# 09_EXP_CN_100PIN.net
KiCad netlist of a schematic drawn in Altium Designer
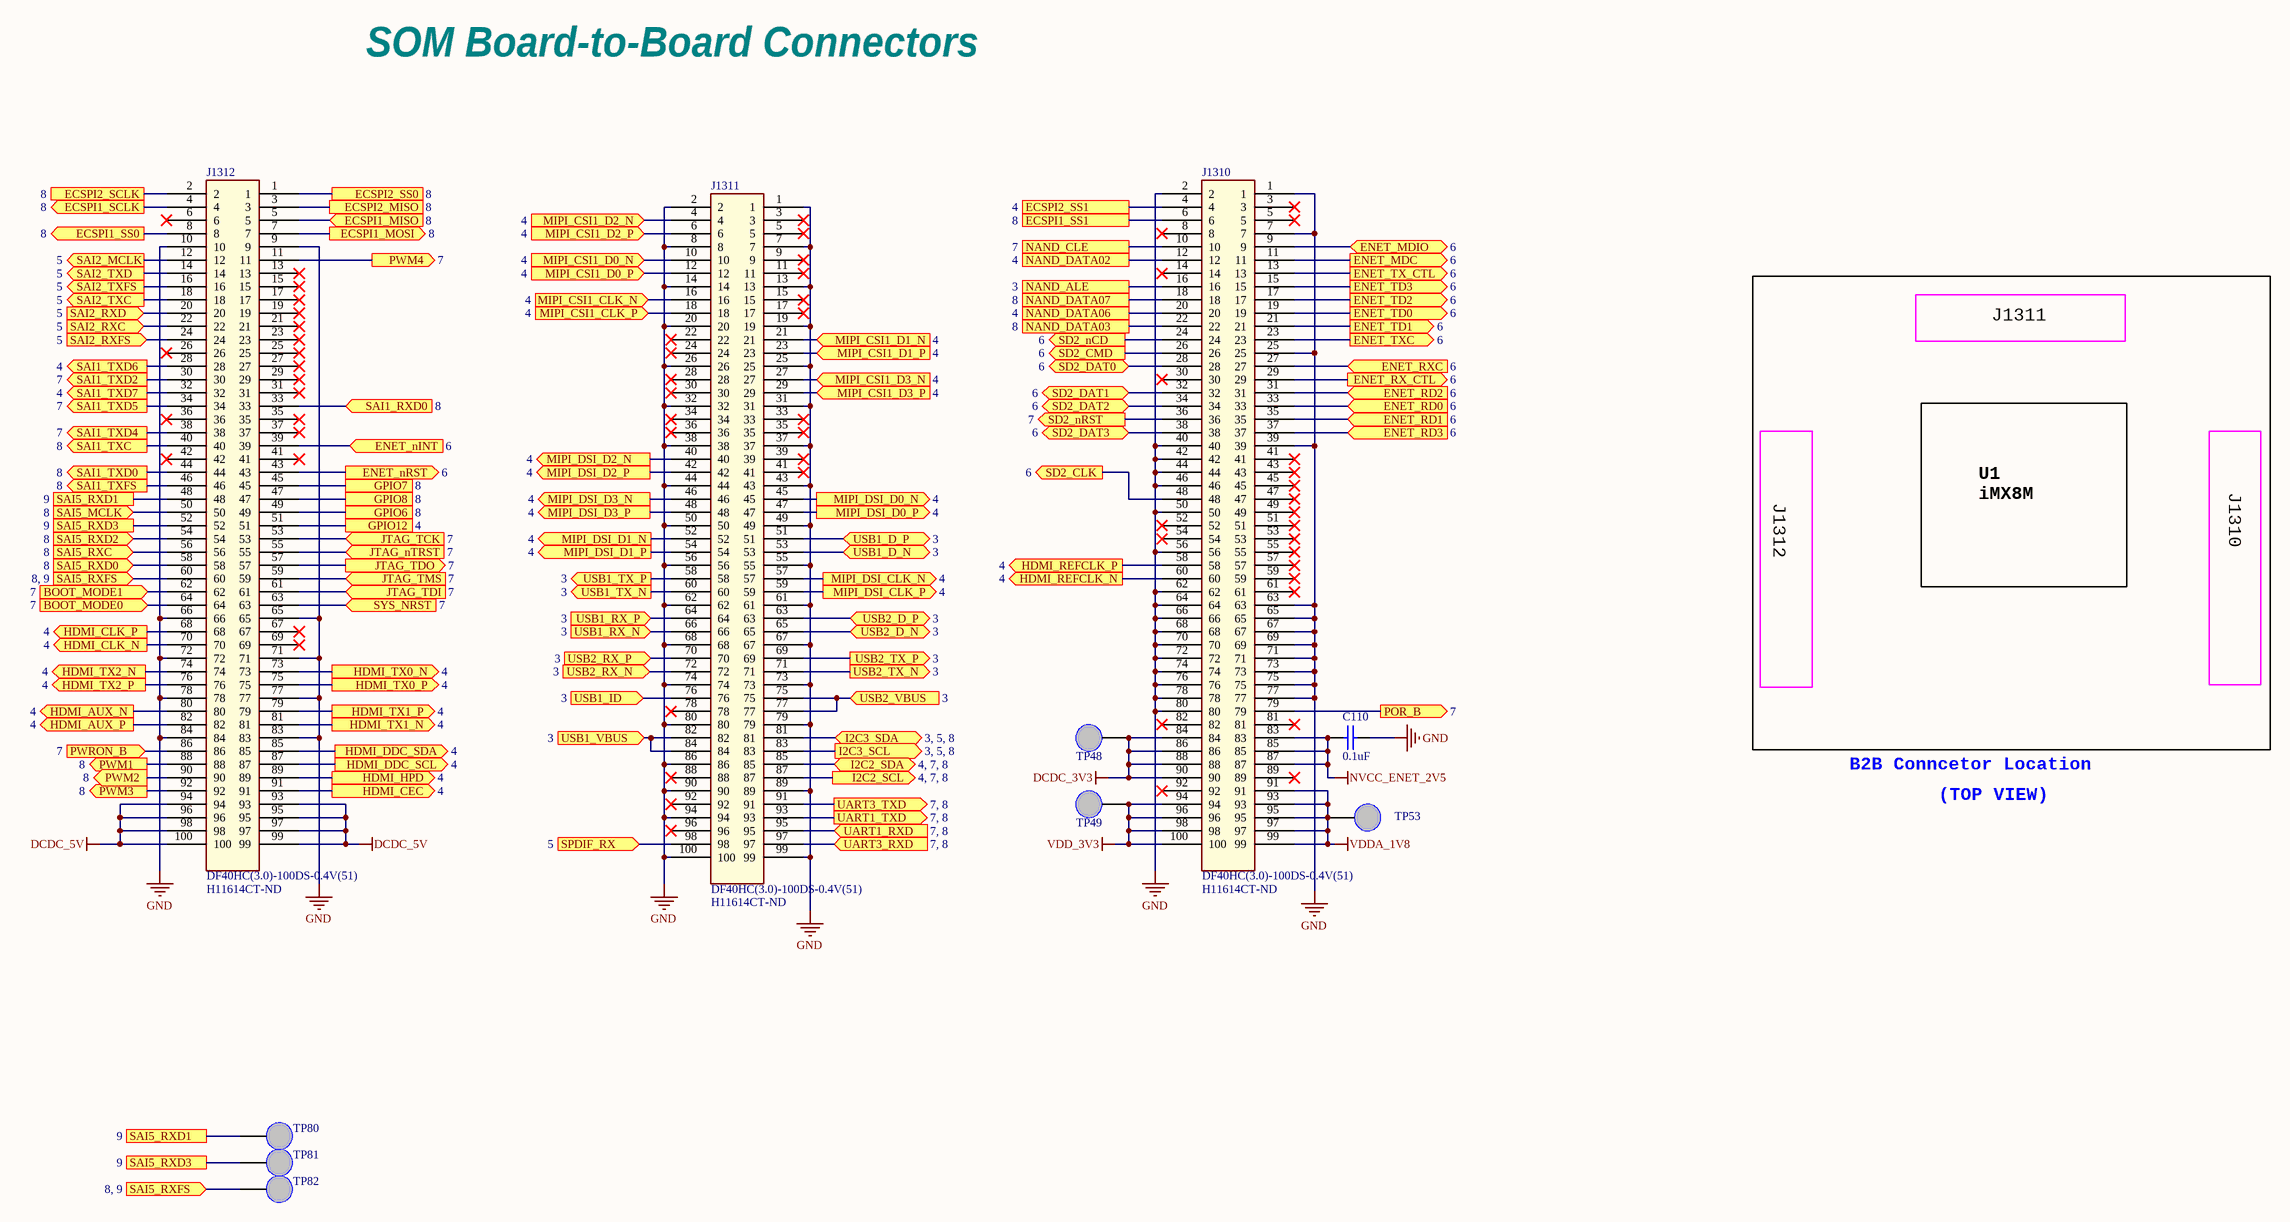
[diagram p0: 09_EXP_CN_100PIN.SchDoc]

(export (version "E")
  (design (tool "Eeschema 10.0.6"))
  (components
    (comp (ref "C110")
      (value "0.1uF")
      (footprint "0201")
      (description "CAP CER 0.1UF 10V 10% X5R 0201")
      (fields (field (name "MPN") "C0603X5R1A104K030BC") (field (name "Comment") "0.1uF/10V"))
      (libsource (lib "links") (part "CAP_0201_0.1uF"))
    )
    (comp (ref "J1310")
      (value "DF40HC(3.0)-100DS-0.4V(51)")
      (footprint "DF40HC-3_0-100DS-0_4V-51")
      (description "CONN HDR 100POS 0.4MM SMD GOLD")
      (fields (field (name "SUPPLIER PART NUMBER 1") "H11614CT-ND"))
      (libsource (lib "SpacePark") (part "CONN_HIROSE-DF40C-100DP-0.4V(51)"))
    )
    (comp (ref "J1311")
      (value "DF40HC(3.0)-100DS-0.4V(51)")
      (footprint "DF40HC-3_0-100DS-0_4V-51")
      (description "CONN HDR 100POS 0.4MM SMD GOLD")
      (fields (field (name "SUPPLIER PART NUMBER 1") "H11614CT-ND"))
      (libsource (lib "SpacePark") (part "CONN_HIROSE-DF40C-100DP-0.4V(51)"))
    )
    (comp (ref "J1312")
      (value "DF40HC(3.0)-100DS-0.4V(51)")
      (footprint "DF40HC-3_0-100DS-0_4V-51")
      (description "CONN HDR 100POS 0.4MM SMD GOLD")
      (fields (field (name "SUPPLIER PART NUMBER 1") "H11614CT-ND"))
      (libsource (lib "SpacePark") (part "CONN_HIROSE-DF40C-100DP-0.4V(51)"))
    )
    (comp (ref "TP48")
      (value "TP NM")
      (footprint "TP_SMD_L")
      (description "TEST POINT (Large)")
      (libsource (lib "links") (part "TP_L"))
    )
    (comp (ref "TP49")
      (value "TP NM")
      (footprint "TP_SMD_L")
      (description "TEST POINT (Large)")
      (libsource (lib "links") (part "TP_L"))
    )
    (comp (ref "TP53")
      (value "TP NM")
      (footprint "TP_SMD_L")
      (description "TEST POINT (Large)")
      (libsource (lib "links") (part "TP_L"))
    )
    (comp (ref "TP80")
      (value "TP NM")
      (footprint "TP_SMD_L")
      (description "TEST POINT (Large)")
      (libsource (lib "links") (part "TP_L"))
    )
    (comp (ref "TP81")
      (value "TP NM")
      (footprint "TP_SMD_L")
      (description "TEST POINT (Large)")
      (libsource (lib "links") (part "TP_L"))
    )
    (comp (ref "TP82")
      (value "TP NM")
      (footprint "TP_SMD_L")
      (description "TEST POINT (Large)")
      (libsource (lib "links") (part "TP_L"))
    )
  )
  (nets
    (net (code "1") (name "/BOOT_MODE0") (class "Default")
      (node (ref "J1312") (pin "64") (pinfunction "64_64") (pintype "passive"))
    )
    (net (code "2") (name "/BOOT_MODE1") (class "Default")
      (node (ref "J1312") (pin "62") (pinfunction "62_62") (pintype "passive"))
    )
    (net (code "3") (name "/ECSPI1_MISO") (class "Default")
      (node (ref "J1312") (pin "5") (pinfunction "5_5") (pintype "passive"))
    )
    (net (code "4") (name "/ECSPI1_MOSI") (class "Default")
      (node (ref "J1312") (pin "7") (pinfunction "7_7") (pintype "passive"))
    )
    (net (code "5") (name "/ECSPI1_SCLK") (class "Default")
      (node (ref "J1312") (pin "4") (pinfunction "4_4") (pintype "passive"))
    )
    (net (code "6") (name "/ECSPI1_SS0") (class "Default")
      (node (ref "J1312") (pin "8") (pinfunction "8_8") (pintype "passive"))
    )
    (net (code "7") (name "/ECSPI1_SS1") (class "Default")
      (node (ref "J1310") (pin "6") (pinfunction "6_6") (pintype "passive"))
    )
    (net (code "8") (name "/ECSPI2_MISO") (class "Default")
      (node (ref "J1312") (pin "3") (pinfunction "3_3") (pintype "passive"))
    )
    (net (code "9") (name "/ECSPI2_SCLK") (class "Default")
      (node (ref "J1312") (pin "2") (pinfunction "2_2") (pintype "passive"))
    )
    (net (code "10") (name "/ECSPI2_SS0") (class "Default")
      (node (ref "J1312") (pin "1") (pinfunction "1_1") (pintype "passive"))
    )
    (net (code "11") (name "/ECSPI2_SS1") (class "Default")
      (node (ref "J1310") (pin "4") (pinfunction "4_4") (pintype "passive"))
    )
    (net (code "12") (name "/ENET_MDC") (class "Default")
      (node (ref "J1310") (pin "11") (pinfunction "11_11") (pintype "passive"))
    )
    (net (code "13") (name "/ENET_MDIO") (class "Default")
      (node (ref "J1310") (pin "9") (pinfunction "9_9") (pintype "passive"))
    )
    (net (code "14") (name "/ENET_RD0") (class "Default")
      (node (ref "J1310") (pin "33") (pinfunction "33_33") (pintype "passive"))
    )
    (net (code "15") (name "/ENET_RD1") (class "Default")
      (node (ref "J1310") (pin "35") (pinfunction "35_35") (pintype "passive"))
    )
    (net (code "16") (name "/ENET_RD2") (class "Default")
      (node (ref "J1310") (pin "31") (pinfunction "31_31") (pintype "passive"))
    )
    (net (code "17") (name "/ENET_RD3") (class "Default")
      (node (ref "J1310") (pin "37") (pinfunction "37_37") (pintype "passive"))
    )
    (net (code "18") (name "/ENET_RXC") (class "Default")
      (node (ref "J1310") (pin "27") (pinfunction "27_27") (pintype "passive"))
    )
    (net (code "19") (name "/ENET_RX_CTL") (class "Default")
      (node (ref "J1310") (pin "29") (pinfunction "29_29") (pintype "passive"))
    )
    (net (code "20") (name "/ENET_TD0") (class "Default")
      (node (ref "J1310") (pin "19") (pinfunction "19_19") (pintype "passive"))
    )
    (net (code "21") (name "/ENET_TD1") (class "Default")
      (node (ref "J1310") (pin "21") (pinfunction "21_21") (pintype "passive"))
    )
    (net (code "22") (name "/ENET_TD2") (class "Default")
      (node (ref "J1310") (pin "17") (pinfunction "17_17") (pintype "passive"))
    )
    (net (code "23") (name "/ENET_TD3") (class "Default")
      (node (ref "J1310") (pin "15") (pinfunction "15_15") (pintype "passive"))
    )
    (net (code "24") (name "/ENET_TXC") (class "Default")
      (node (ref "J1310") (pin "23") (pinfunction "23_23") (pintype "passive"))
    )
    (net (code "25") (name "/ENET_TX_CTL") (class "Default")
      (node (ref "J1310") (pin "13") (pinfunction "13_13") (pintype "passive"))
    )
    (net (code "26") (name "/ENET_nINT") (class "Default")
      (node (ref "J1312") (pin "39") (pinfunction "39_39") (pintype "passive"))
    )
    (net (code "27") (name "/ENET_nRST") (class "Default")
      (node (ref "J1312") (pin "43") (pinfunction "43_43") (pintype "passive"))
    )
    (net (code "28") (name "/GPIO6") (class "Default")
      (node (ref "J1312") (pin "49") (pinfunction "49_49") (pintype "passive"))
    )
    (net (code "29") (name "/GPIO7") (class "Default")
      (node (ref "J1312") (pin "45") (pinfunction "45_45") (pintype "passive"))
    )
    (net (code "30") (name "/GPIO8") (class "Default")
      (node (ref "J1312") (pin "47") (pinfunction "47_47") (pintype "passive"))
    )
    (net (code "31") (name "/GPIO12") (class "Default")
      (node (ref "J1312") (pin "51") (pinfunction "51_51") (pintype "passive"))
    )
    (net (code "32") (name "/HDMI_AUX_N") (class "Default")
      (node (ref "J1312") (pin "80") (pinfunction "80_80") (pintype "passive"))
    )
    (net (code "33") (name "/HDMI_AUX_P") (class "Default")
      (node (ref "J1312") (pin "82") (pinfunction "82_82") (pintype "passive"))
    )
    (net (code "34") (name "/HDMI_CEC") (class "Default")
      (node (ref "J1312") (pin "91") (pinfunction "91_91") (pintype "passive"))
    )
    (net (code "35") (name "/HDMI_CLK_N") (class "Default")
      (node (ref "J1312") (pin "70") (pinfunction "70_70") (pintype "passive"))
    )
    (net (code "36") (name "/HDMI_CLK_P") (class "Default")
      (node (ref "J1312") (pin "68") (pinfunction "68_68") (pintype "passive"))
    )
    (net (code "37") (name "/HDMI_DDC_SCL") (class "Default")
      (node (ref "J1312") (pin "87") (pinfunction "87_87") (pintype "passive"))
    )
    (net (code "38") (name "/HDMI_DDC_SDA") (class "Default")
      (node (ref "J1312") (pin "85") (pinfunction "85_85") (pintype "passive"))
    )
    (net (code "39") (name "/HDMI_HPD") (class "Default")
      (node (ref "J1312") (pin "89") (pinfunction "89_89") (pintype "passive"))
    )
    (net (code "40") (name "/HDMI_REFCLK_N") (class "Default")
      (node (ref "J1310") (pin "60") (pinfunction "60_60") (pintype "passive"))
    )
    (net (code "41") (name "/HDMI_REFCLK_P") (class "Default")
      (node (ref "J1310") (pin "58") (pinfunction "58_58") (pintype "passive"))
    )
    (net (code "42") (name "/HDMI_TX0_N") (class "Default")
      (node (ref "J1312") (pin "73") (pinfunction "73_73") (pintype "passive"))
    )
    (net (code "43") (name "/HDMI_TX0_P") (class "Default")
      (node (ref "J1312") (pin "75") (pinfunction "75_75") (pintype "passive"))
    )
    (net (code "44") (name "/HDMI_TX1_N") (class "Default")
      (node (ref "J1312") (pin "81") (pinfunction "81_81") (pintype "passive"))
    )
    (net (code "45") (name "/HDMI_TX1_P") (class "Default")
      (node (ref "J1312") (pin "79") (pinfunction "79_79") (pintype "passive"))
    )
    (net (code "46") (name "/HDMI_TX2_N") (class "Default")
      (node (ref "J1312") (pin "74") (pinfunction "74_74") (pintype "passive"))
    )
    (net (code "47") (name "/HDMI_TX2_P") (class "Default")
      (node (ref "J1312") (pin "76") (pinfunction "76_76") (pintype "passive"))
    )
    (net (code "48") (name "/I2C2_SCL") (class "Default")
      (node (ref "J1311") (pin "87") (pinfunction "87_87") (pintype "passive"))
    )
    (net (code "49") (name "/I2C2_SDA") (class "Default")
      (node (ref "J1311") (pin "85") (pinfunction "85_85") (pintype "passive"))
    )
    (net (code "50") (name "/I2C3_SCL") (class "Default")
      (node (ref "J1311") (pin "83") (pinfunction "83_83") (pintype "passive"))
    )
    (net (code "51") (name "/I2C3_SDA") (class "Default")
      (node (ref "J1311") (pin "81") (pinfunction "81_81") (pintype "passive"))
    )
    (net (code "52") (name "/JTAG_TCK") (class "Default")
      (node (ref "J1312") (pin "53") (pinfunction "53_53") (pintype "passive"))
    )
    (net (code "53") (name "/JTAG_TDI") (class "Default")
      (node (ref "J1312") (pin "61") (pinfunction "61_61") (pintype "passive"))
    )
    (net (code "54") (name "/JTAG_TDO") (class "Default")
      (node (ref "J1312") (pin "57") (pinfunction "57_57") (pintype "passive"))
    )
    (net (code "55") (name "/JTAG_TMS") (class "Default")
      (node (ref "J1312") (pin "59") (pinfunction "59_59") (pintype "passive"))
    )
    (net (code "56") (name "/JTAG_nTRST") (class "Default")
      (node (ref "J1312") (pin "55") (pinfunction "55_55") (pintype "passive"))
    )
    (net (code "57") (name "/MIPI_CSI1_CLK_N") (class "Default")
      (node (ref "J1311") (pin "16") (pinfunction "16_16") (pintype "passive"))
    )
    (net (code "58") (name "/MIPI_CSI1_CLK_P") (class "Default")
      (node (ref "J1311") (pin "18") (pinfunction "18_18") (pintype "passive"))
    )
    (net (code "59") (name "/MIPI_CSI1_D0_N") (class "Default")
      (node (ref "J1311") (pin "10") (pinfunction "10_10") (pintype "passive"))
    )
    (net (code "60") (name "/MIPI_CSI1_D0_P") (class "Default")
      (node (ref "J1311") (pin "12") (pinfunction "12_12") (pintype "passive"))
    )
    (net (code "61") (name "/MIPI_CSI1_D1_N") (class "Default")
      (node (ref "J1311") (pin "21") (pinfunction "21_21") (pintype "passive"))
    )
    (net (code "62") (name "/MIPI_CSI1_D1_P") (class "Default")
      (node (ref "J1311") (pin "23") (pinfunction "23_23") (pintype "passive"))
    )
    (net (code "63") (name "/MIPI_CSI1_D2_N") (class "Default")
      (node (ref "J1311") (pin "4") (pinfunction "4_4") (pintype "passive"))
    )
    (net (code "64") (name "/MIPI_CSI1_D2_P") (class "Default")
      (node (ref "J1311") (pin "6") (pinfunction "6_6") (pintype "passive"))
    )
    (net (code "65") (name "/MIPI_CSI1_D3_N") (class "Default")
      (node (ref "J1311") (pin "27") (pinfunction "27_27") (pintype "passive"))
    )
    (net (code "66") (name "/MIPI_CSI1_D3_P") (class "Default")
      (node (ref "J1311") (pin "29") (pinfunction "29_29") (pintype "passive"))
    )
    (net (code "67") (name "/MIPI_DSI_CLK_N") (class "Default")
      (node (ref "J1311") (pin "57") (pinfunction "57_57") (pintype "passive"))
    )
    (net (code "68") (name "/MIPI_DSI_CLK_P") (class "Default")
      (node (ref "J1311") (pin "59") (pinfunction "59_59") (pintype "passive"))
    )
    (net (code "69") (name "/MIPI_DSI_D0_N") (class "Default")
      (node (ref "J1311") (pin "45") (pinfunction "45_45") (pintype "passive"))
    )
    (net (code "70") (name "/MIPI_DSI_D0_P") (class "Default")
      (node (ref "J1311") (pin "47") (pinfunction "47_47") (pintype "passive"))
    )
    (net (code "71") (name "/MIPI_DSI_D1_N") (class "Default")
      (node (ref "J1311") (pin "52") (pinfunction "52_52") (pintype "passive"))
    )
    (net (code "72") (name "/MIPI_DSI_D1_P") (class "Default")
      (node (ref "J1311") (pin "54") (pinfunction "54_54") (pintype "passive"))
    )
    (net (code "73") (name "/MIPI_DSI_D2_N") (class "Default")
      (node (ref "J1311") (pin "40") (pinfunction "40_40") (pintype "passive"))
    )
    (net (code "74") (name "/MIPI_DSI_D2_P") (class "Default")
      (node (ref "J1311") (pin "42") (pinfunction "42_42") (pintype "passive"))
    )
    (net (code "75") (name "/MIPI_DSI_D3_N") (class "Default")
      (node (ref "J1311") (pin "46") (pinfunction "46_46") (pintype "passive"))
    )
    (net (code "76") (name "/MIPI_DSI_D3_P") (class "Default")
      (node (ref "J1311") (pin "48") (pinfunction "48_48") (pintype "passive"))
    )
    (net (code "77") (name "/NAND_ALE") (class "Default")
      (node (ref "J1310") (pin "16") (pinfunction "16_16") (pintype "passive"))
    )
    (net (code "78") (name "/NAND_CLE") (class "Default")
      (node (ref "J1310") (pin "10") (pinfunction "10_10") (pintype "passive"))
    )
    (net (code "79") (name "/NAND_DATA02") (class "Default")
      (node (ref "J1310") (pin "12") (pinfunction "12_12") (pintype "passive"))
    )
    (net (code "80") (name "/NAND_DATA03") (class "Default")
      (node (ref "J1310") (pin "22") (pinfunction "22_22") (pintype "passive"))
    )
    (net (code "81") (name "/NAND_DATA06") (class "Default")
      (node (ref "J1310") (pin "20") (pinfunction "20_20") (pintype "passive"))
    )
    (net (code "82") (name "/NAND_DATA07") (class "Default")
      (node (ref "J1310") (pin "18") (pinfunction "18_18") (pintype "passive"))
    )
    (net (code "83") (name "/POR_B") (class "Default")
      (node (ref "J1310") (pin "79") (pinfunction "79_79") (pintype "passive"))
    )
    (net (code "84") (name "/PWM1") (class "Default")
      (node (ref "J1312") (pin "88") (pinfunction "88_88") (pintype "passive"))
    )
    (net (code "85") (name "/PWM2") (class "Default")
      (node (ref "J1312") (pin "90") (pinfunction "90_90") (pintype "passive"))
    )
    (net (code "86") (name "/PWM3") (class "Default")
      (node (ref "J1312") (pin "92") (pinfunction "92_92") (pintype "passive"))
    )
    (net (code "87") (name "/PWM4") (class "Default")
      (node (ref "J1312") (pin "11") (pinfunction "11_11") (pintype "passive"))
    )
    (net (code "88") (name "/PWRON_B") (class "Default")
      (node (ref "J1312") (pin "86") (pinfunction "86_86") (pintype "passive"))
    )
    (net (code "89") (name "/SAI1_RXD0") (class "Default")
      (node (ref "J1312") (pin "33") (pinfunction "33_33") (pintype "passive"))
    )
    (net (code "90") (name "/SAI1_TXC") (class "Default")
      (node (ref "J1312") (pin "40") (pinfunction "40_40") (pintype "passive"))
    )
    (net (code "91") (name "/SAI1_TXD0") (class "Default")
      (node (ref "J1312") (pin "44") (pinfunction "44_44") (pintype "passive"))
    )
    (net (code "92") (name "/SAI1_TXD2") (class "Default")
      (node (ref "J1312") (pin "30") (pinfunction "30_30") (pintype "passive"))
    )
    (net (code "93") (name "/SAI1_TXD4") (class "Default")
      (node (ref "J1312") (pin "38") (pinfunction "38_38") (pintype "passive"))
    )
    (net (code "94") (name "/SAI1_TXD5") (class "Default")
      (node (ref "J1312") (pin "34") (pinfunction "34_34") (pintype "passive"))
    )
    (net (code "95") (name "/SAI1_TXD6") (class "Default")
      (node (ref "J1312") (pin "28") (pinfunction "28_28") (pintype "passive"))
    )
    (net (code "96") (name "/SAI1_TXD7") (class "Default")
      (node (ref "J1312") (pin "32") (pinfunction "32_32") (pintype "passive"))
    )
    (net (code "97") (name "/SAI1_TXFS") (class "Default")
      (node (ref "J1312") (pin "46") (pinfunction "46_46") (pintype "passive"))
    )
    (net (code "98") (name "/SAI2_MCLK") (class "Default")
      (node (ref "J1312") (pin "12") (pinfunction "12_12") (pintype "passive"))
    )
    (net (code "99") (name "/SAI2_RXC") (class "Default")
      (node (ref "J1312") (pin "22") (pinfunction "22_22") (pintype "passive"))
    )
    (net (code "100") (name "/SAI2_RXD") (class "Default")
      (node (ref "J1312") (pin "20") (pinfunction "20_20") (pintype "passive"))
    )
    (net (code "101") (name "/SAI2_RXFS") (class "Default")
      (node (ref "J1312") (pin "24") (pinfunction "24_24") (pintype "passive"))
    )
    (net (code "102") (name "/SAI2_TXC") (class "Default")
      (node (ref "J1312") (pin "18") (pinfunction "18_18") (pintype "passive"))
    )
    (net (code "103") (name "/SAI2_TXD") (class "Default")
      (node (ref "J1312") (pin "14") (pinfunction "14_14") (pintype "passive"))
    )
    (net (code "104") (name "/SAI2_TXFS") (class "Default")
      (node (ref "J1312") (pin "16") (pinfunction "16_16") (pintype "passive"))
    )
    (net (code "105") (name "/SAI5_MCLK") (class "Default")
      (node (ref "J1312") (pin "50") (pinfunction "50_50") (pintype "passive"))
    )
    (net (code "106") (name "/SAI5_RXC") (class "Default")
      (node (ref "J1312") (pin "56") (pinfunction "56_56") (pintype "passive"))
    )
    (net (code "107") (name "/SAI5_RXD0") (class "Default")
      (node (ref "J1312") (pin "58") (pinfunction "58_58") (pintype "passive"))
    )
    (net (code "108") (name "/SAI5_RXD1") (class "Default")
      (node (ref "J1312") (pin "48") (pinfunction "48_48") (pintype "passive"))
      (node (ref "TP80") (pin "1") (pinfunction "1_1") (pintype "passive"))
    )
    (net (code "109") (name "/SAI5_RXD2") (class "Default")
      (node (ref "J1312") (pin "54") (pinfunction "54_54") (pintype "passive"))
    )
    (net (code "110") (name "/SAI5_RXD3") (class "Default")
      (node (ref "J1312") (pin "52") (pinfunction "52_52") (pintype "passive"))
      (node (ref "TP81") (pin "1") (pinfunction "1_1") (pintype "passive"))
    )
    (net (code "111") (name "/SAI5_RXFS") (class "Default")
      (node (ref "J1312") (pin "60") (pinfunction "60_60") (pintype "passive"))
      (node (ref "TP82") (pin "1") (pinfunction "1_1") (pintype "passive"))
    )
    (net (code "112") (name "/SD2_CLK") (class "Default")
      (node (ref "J1310") (pin "48") (pinfunction "48_48") (pintype "passive"))
    )
    (net (code "113") (name "/SD2_CMD") (class "Default")
      (node (ref "J1310") (pin "26") (pinfunction "26_26") (pintype "passive"))
    )
    (net (code "114") (name "/SD2_DAT0") (class "Default")
      (node (ref "J1310") (pin "28") (pinfunction "28_28") (pintype "passive"))
    )
    (net (code "115") (name "/SD2_DAT1") (class "Default")
      (node (ref "J1310") (pin "32") (pinfunction "32_32") (pintype "passive"))
    )
    (net (code "116") (name "/SD2_DAT2") (class "Default")
      (node (ref "J1310") (pin "34") (pinfunction "34_34") (pintype "passive"))
    )
    (net (code "117") (name "/SD2_DAT3") (class "Default")
      (node (ref "J1310") (pin "38") (pinfunction "38_38") (pintype "passive"))
    )
    (net (code "118") (name "/SD2_nCD") (class "Default")
      (node (ref "J1310") (pin "24") (pinfunction "24_24") (pintype "passive"))
    )
    (net (code "119") (name "/SD2_nRST") (class "Default")
      (node (ref "J1310") (pin "36") (pinfunction "36_36") (pintype "passive"))
    )
    (net (code "120") (name "/SPDIF_RX") (class "Default")
      (node (ref "J1311") (pin "98") (pinfunction "98_98") (pintype "passive"))
    )
    (net (code "121") (name "/SYS_NRST") (class "Default")
      (node (ref "J1312") (pin "63") (pinfunction "63_63") (pintype "passive"))
    )
    (net (code "122") (name "/UART1_RXD") (class "Default")
      (node (ref "J1311") (pin "95") (pinfunction "95_95") (pintype "passive"))
    )
    (net (code "123") (name "/UART1_TXD") (class "Default")
      (node (ref "J1311") (pin "93") (pinfunction "93_93") (pintype "passive"))
    )
    (net (code "124") (name "/UART3_RXD") (class "Default")
      (node (ref "J1311") (pin "97") (pinfunction "97_97") (pintype "passive"))
    )
    (net (code "125") (name "/UART3_TXD") (class "Default")
      (node (ref "J1311") (pin "91") (pinfunction "91_91") (pintype "passive"))
    )
    (net (code "126") (name "/USB1_D_N") (class "Default")
      (node (ref "J1311") (pin "53") (pinfunction "53_53") (pintype "passive"))
    )
    (net (code "127") (name "/USB1_D_P") (class "Default")
      (node (ref "J1311") (pin "51") (pinfunction "51_51") (pintype "passive"))
    )
    (net (code "128") (name "/USB1_ID") (class "Default")
      (node (ref "J1311") (pin "76") (pinfunction "76_76") (pintype "passive"))
    )
    (net (code "129") (name "/USB1_RX_N") (class "Default")
      (node (ref "J1311") (pin "66") (pinfunction "66_66") (pintype "passive"))
    )
    (net (code "130") (name "/USB1_RX_P") (class "Default")
      (node (ref "J1311") (pin "64") (pinfunction "64_64") (pintype "passive"))
    )
    (net (code "131") (name "/USB1_TX_N") (class "Default")
      (node (ref "J1311") (pin "60") (pinfunction "60_60") (pintype "passive"))
    )
    (net (code "132") (name "/USB1_TX_P") (class "Default")
      (node (ref "J1311") (pin "58") (pinfunction "58_58") (pintype "passive"))
    )
    (net (code "133") (name "/USB1_VBUS") (class "Default")
      (node (ref "J1311") (pin "82") (pinfunction "82_82") (pintype "passive"))
      (node (ref "J1311") (pin "84") (pinfunction "84_84") (pintype "passive"))
    )
    (net (code "134") (name "/USB2_D_N") (class "Default")
      (node (ref "J1311") (pin "65") (pinfunction "65_65") (pintype "passive"))
    )
    (net (code "135") (name "/USB2_D_P") (class "Default")
      (node (ref "J1311") (pin "63") (pinfunction "63_63") (pintype "passive"))
    )
    (net (code "136") (name "/USB2_RX_N") (class "Default")
      (node (ref "J1311") (pin "72") (pinfunction "72_72") (pintype "passive"))
    )
    (net (code "137") (name "/USB2_RX_P") (class "Default")
      (node (ref "J1311") (pin "70") (pinfunction "70_70") (pintype "passive"))
    )
    (net (code "138") (name "/USB2_TX_N") (class "Default")
      (node (ref "J1311") (pin "71") (pinfunction "71_71") (pintype "passive"))
    )
    (net (code "139") (name "/USB2_TX_P") (class "Default")
      (node (ref "J1311") (pin "69") (pinfunction "69_69") (pintype "passive"))
    )
    (net (code "140") (name "/USB2_VBUS") (class "Default")
      (node (ref "J1311") (pin "75") (pinfunction "75_75") (pintype "passive"))
      (node (ref "J1311") (pin "77") (pinfunction "77_77") (pintype "passive"))
    )
    (net (code "141") (name "DCDC_3V3") (class "Default")
      (node (ref "J1310") (pin "84") (pinfunction "84_84") (pintype "passive"))
      (node (ref "J1310") (pin "86") (pinfunction "86_86") (pintype "passive"))
      (node (ref "J1310") (pin "88") (pinfunction "88_88") (pintype "passive"))
      (node (ref "J1310") (pin "90") (pinfunction "90_90") (pintype "passive"))
      (node (ref "TP48") (pin "1") (pinfunction "1_1") (pintype "passive"))
    )
    (net (code "142") (name "DCDC_5V") (class "Default")
      (node (ref "J1312") (pin "100") (pinfunction "100_100") (pintype "passive"))
      (node (ref "J1312") (pin "93") (pinfunction "93_93") (pintype "passive"))
      (node (ref "J1312") (pin "94") (pinfunction "94_94") (pintype "passive"))
      (node (ref "J1312") (pin "95") (pinfunction "95_95") (pintype "passive"))
      (node (ref "J1312") (pin "96") (pinfunction "96_96") (pintype "passive"))
      (node (ref "J1312") (pin "97") (pinfunction "97_97") (pintype "passive"))
      (node (ref "J1312") (pin "98") (pinfunction "98_98") (pintype "passive"))
      (node (ref "J1312") (pin "99") (pinfunction "99_99") (pintype "passive"))
    )
    (net (code "143") (name "GND") (class "Default")
      (node (ref "C110") (pin "2") (pinfunction "2_2") (pintype "passive"))
      (node (ref "J1310") (pin "1") (pinfunction "1_1") (pintype "passive"))
      (node (ref "J1310") (pin "2") (pinfunction "2_2") (pintype "passive"))
      (node (ref "J1310") (pin "25") (pinfunction "25_25") (pintype "passive"))
      (node (ref "J1310") (pin "39") (pinfunction "39_39") (pintype "passive"))
      (node (ref "J1310") (pin "40") (pinfunction "40_40") (pintype "passive"))
      (node (ref "J1310") (pin "42") (pinfunction "42_42") (pintype "passive"))
      (node (ref "J1310") (pin "44") (pinfunction "44_44") (pintype "passive"))
      (node (ref "J1310") (pin "46") (pinfunction "46_46") (pintype "passive"))
      (node (ref "J1310") (pin "50") (pinfunction "50_50") (pintype "passive"))
      (node (ref "J1310") (pin "56") (pinfunction "56_56") (pintype "passive"))
      (node (ref "J1310") (pin "62") (pinfunction "62_62") (pintype "passive"))
      (node (ref "J1310") (pin "63") (pinfunction "63_63") (pintype "passive"))
      (node (ref "J1310") (pin "64") (pinfunction "64_64") (pintype "passive"))
      (node (ref "J1310") (pin "65") (pinfunction "65_65") (pintype "passive"))
      (node (ref "J1310") (pin "66") (pinfunction "66_66") (pintype "passive"))
      (node (ref "J1310") (pin "67") (pinfunction "67_67") (pintype "passive"))
      (node (ref "J1310") (pin "68") (pinfunction "68_68") (pintype "passive"))
      (node (ref "J1310") (pin "69") (pinfunction "69_69") (pintype "passive"))
      (node (ref "J1310") (pin "7") (pinfunction "7_7") (pintype "passive"))
      (node (ref "J1310") (pin "70") (pinfunction "70_70") (pintype "passive"))
      (node (ref "J1310") (pin "71") (pinfunction "71_71") (pintype "passive"))
      (node (ref "J1310") (pin "72") (pinfunction "72_72") (pintype "passive"))
      (node (ref "J1310") (pin "73") (pinfunction "73_73") (pintype "passive"))
      (node (ref "J1310") (pin "74") (pinfunction "74_74") (pintype "passive"))
      (node (ref "J1310") (pin "75") (pinfunction "75_75") (pintype "passive"))
      (node (ref "J1310") (pin "76") (pinfunction "76_76") (pintype "passive"))
      (node (ref "J1310") (pin "77") (pinfunction "77_77") (pintype "passive"))
      (node (ref "J1310") (pin "78") (pinfunction "78_78") (pintype "passive"))
      (node (ref "J1310") (pin "80") (pinfunction "80_80") (pintype "passive"))
      (node (ref "J1311") (pin "1") (pinfunction "1_1") (pintype "passive"))
      (node (ref "J1311") (pin "100") (pinfunction "100_100") (pintype "passive"))
      (node (ref "J1311") (pin "13") (pinfunction "13_13") (pintype "passive"))
      (node (ref "J1311") (pin "14") (pinfunction "14_14") (pintype "passive"))
      (node (ref "J1311") (pin "19") (pinfunction "19_19") (pintype "passive"))
      (node (ref "J1311") (pin "2") (pinfunction "2_2") (pintype "passive"))
      (node (ref "J1311") (pin "20") (pinfunction "20_20") (pintype "passive"))
      (node (ref "J1311") (pin "25") (pinfunction "25_25") (pintype "passive"))
      (node (ref "J1311") (pin "26") (pinfunction "26_26") (pintype "passive"))
      (node (ref "J1311") (pin "31") (pinfunction "31_31") (pintype "passive"))
      (node (ref "J1311") (pin "32") (pinfunction "32_32") (pintype "passive"))
      (node (ref "J1311") (pin "37") (pinfunction "37_37") (pintype "passive"))
      (node (ref "J1311") (pin "38") (pinfunction "38_38") (pintype "passive"))
      (node (ref "J1311") (pin "43") (pinfunction "43_43") (pintype "passive"))
      (node (ref "J1311") (pin "44") (pinfunction "44_44") (pintype "passive"))
      (node (ref "J1311") (pin "49") (pinfunction "49_49") (pintype "passive"))
      (node (ref "J1311") (pin "50") (pinfunction "50_50") (pintype "passive"))
      (node (ref "J1311") (pin "55") (pinfunction "55_55") (pintype "passive"))
      (node (ref "J1311") (pin "56") (pinfunction "56_56") (pintype "passive"))
      (node (ref "J1311") (pin "61") (pinfunction "61_61") (pintype "passive"))
      (node (ref "J1311") (pin "62") (pinfunction "62_62") (pintype "passive"))
      (node (ref "J1311") (pin "67") (pinfunction "67_67") (pintype "passive"))
      (node (ref "J1311") (pin "68") (pinfunction "68_68") (pintype "passive"))
      (node (ref "J1311") (pin "7") (pinfunction "7_7") (pintype "passive"))
      (node (ref "J1311") (pin "73") (pinfunction "73_73") (pintype "passive"))
      (node (ref "J1311") (pin "74") (pinfunction "74_74") (pintype "passive"))
      (node (ref "J1311") (pin "79") (pinfunction "79_79") (pintype "passive"))
      (node (ref "J1311") (pin "8") (pinfunction "8_8") (pintype "passive"))
      (node (ref "J1311") (pin "80") (pinfunction "80_80") (pintype "passive"))
      (node (ref "J1311") (pin "86") (pinfunction "86_86") (pintype "passive"))
      (node (ref "J1311") (pin "89") (pinfunction "89_89") (pintype "passive"))
      (node (ref "J1311") (pin "90") (pinfunction "90_90") (pintype "passive"))
      (node (ref "J1311") (pin "94") (pinfunction "94_94") (pintype "passive"))
      (node (ref "J1311") (pin "99") (pinfunction "99_99") (pintype "passive"))
      (node (ref "J1312") (pin "10") (pinfunction "10_10") (pintype "passive"))
      (node (ref "J1312") (pin "65") (pinfunction "65_65") (pintype "passive"))
      (node (ref "J1312") (pin "66") (pinfunction "66_66") (pintype "passive"))
      (node (ref "J1312") (pin "71") (pinfunction "71_71") (pintype "passive"))
      (node (ref "J1312") (pin "72") (pinfunction "72_72") (pintype "passive"))
      (node (ref "J1312") (pin "77") (pinfunction "77_77") (pintype "passive"))
      (node (ref "J1312") (pin "78") (pinfunction "78_78") (pintype "passive"))
      (node (ref "J1312") (pin "83") (pinfunction "83_83") (pintype "passive"))
      (node (ref "J1312") (pin "84") (pinfunction "84_84") (pintype "passive"))
      (node (ref "J1312") (pin "9") (pinfunction "9_9") (pintype "passive"))
    )
    (net (code "144") (name "NVCC_ENET_2V5") (class "Default")
      (node (ref "C110") (pin "1") (pinfunction "1_1") (pintype "passive"))
      (node (ref "J1310") (pin "83") (pinfunction "83_83") (pintype "passive"))
      (node (ref "J1310") (pin "85") (pinfunction "85_85") (pintype "passive"))
      (node (ref "J1310") (pin "87") (pinfunction "87_87") (pintype "passive"))
    )
    (net (code "145") (name "VDDA_1V8") (class "Default")
      (node (ref "J1310") (pin "91") (pinfunction "91_91") (pintype "passive"))
      (node (ref "J1310") (pin "93") (pinfunction "93_93") (pintype "passive"))
      (node (ref "J1310") (pin "95") (pinfunction "95_95") (pintype "passive"))
      (node (ref "J1310") (pin "97") (pinfunction "97_97") (pintype "passive"))
      (node (ref "J1310") (pin "99") (pinfunction "99_99") (pintype "passive"))
      (node (ref "TP53") (pin "1") (pinfunction "1_1") (pintype "passive"))
    )
    (net (code "146") (name "VDD_3V3") (class "Default")
      (node (ref "J1310") (pin "100") (pinfunction "100_100") (pintype "passive"))
      (node (ref "J1310") (pin "94") (pinfunction "94_94") (pintype "passive"))
      (node (ref "J1310") (pin "96") (pinfunction "96_96") (pintype "passive"))
      (node (ref "J1310") (pin "98") (pinfunction "98_98") (pintype "passive"))
      (node (ref "TP49") (pin "1") (pinfunction "1_1") (pintype "passive"))
    )
    (net (code "147") (name "unconnected-(J1310-Pad3)") (class "Default")
      (node (ref "J1310") (pin "3") (pinfunction "3_3") (pintype "passive+no_connect"))
    )
    (net (code "148") (name "unconnected-(J1310-Pad5)") (class "Default")
      (node (ref "J1310") (pin "5") (pinfunction "5_5") (pintype "passive+no_connect"))
    )
    (net (code "149") (name "unconnected-(J1310-Pad8)") (class "Default")
      (node (ref "J1310") (pin "8") (pinfunction "8_8") (pintype "passive+no_connect"))
    )
    (net (code "150") (name "unconnected-(J1310-Pad14)") (class "Default")
      (node (ref "J1310") (pin "14") (pinfunction "14_14") (pintype "passive+no_connect"))
    )
    (net (code "151") (name "unconnected-(J1310-Pad30)") (class "Default")
      (node (ref "J1310") (pin "30") (pinfunction "30_30") (pintype "passive+no_connect"))
    )
    (net (code "152") (name "unconnected-(J1310-Pad41)") (class "Default")
      (node (ref "J1310") (pin "41") (pinfunction "41_41") (pintype "passive+no_connect"))
    )
    (net (code "153") (name "unconnected-(J1310-Pad43)") (class "Default")
      (node (ref "J1310") (pin "43") (pinfunction "43_43") (pintype "passive+no_connect"))
    )
    (net (code "154") (name "unconnected-(J1310-Pad45)") (class "Default")
      (node (ref "J1310") (pin "45") (pinfunction "45_45") (pintype "passive+no_connect"))
    )
    (net (code "155") (name "unconnected-(J1310-Pad47)") (class "Default")
      (node (ref "J1310") (pin "47") (pinfunction "47_47") (pintype "passive+no_connect"))
    )
    (net (code "156") (name "unconnected-(J1310-Pad49)") (class "Default")
      (node (ref "J1310") (pin "49") (pinfunction "49_49") (pintype "passive+no_connect"))
    )
    (net (code "157") (name "unconnected-(J1310-Pad51)") (class "Default")
      (node (ref "J1310") (pin "51") (pinfunction "51_51") (pintype "passive+no_connect"))
    )
    (net (code "158") (name "unconnected-(J1310-Pad52)") (class "Default")
      (node (ref "J1310") (pin "52") (pinfunction "52_52") (pintype "passive+no_connect"))
    )
    (net (code "159") (name "unconnected-(J1310-Pad53)") (class "Default")
      (node (ref "J1310") (pin "53") (pinfunction "53_53") (pintype "passive+no_connect"))
    )
    (net (code "160") (name "unconnected-(J1310-Pad54)") (class "Default")
      (node (ref "J1310") (pin "54") (pinfunction "54_54") (pintype "passive+no_connect"))
    )
    (net (code "161") (name "unconnected-(J1310-Pad55)") (class "Default")
      (node (ref "J1310") (pin "55") (pinfunction "55_55") (pintype "passive+no_connect"))
    )
    (net (code "162") (name "unconnected-(J1310-Pad57)") (class "Default")
      (node (ref "J1310") (pin "57") (pinfunction "57_57") (pintype "passive+no_connect"))
    )
    (net (code "163") (name "unconnected-(J1310-Pad59)") (class "Default")
      (node (ref "J1310") (pin "59") (pinfunction "59_59") (pintype "passive+no_connect"))
    )
    (net (code "164") (name "unconnected-(J1310-Pad61)") (class "Default")
      (node (ref "J1310") (pin "61") (pinfunction "61_61") (pintype "passive+no_connect"))
    )
    (net (code "165") (name "unconnected-(J1310-Pad81)") (class "Default")
      (node (ref "J1310") (pin "81") (pinfunction "81_81") (pintype "passive+no_connect"))
    )
    (net (code "166") (name "unconnected-(J1310-Pad82)") (class "Default")
      (node (ref "J1310") (pin "82") (pinfunction "82_82") (pintype "passive+no_connect"))
    )
    (net (code "167") (name "unconnected-(J1310-Pad89)") (class "Default")
      (node (ref "J1310") (pin "89") (pinfunction "89_89") (pintype "passive+no_connect"))
    )
    (net (code "168") (name "unconnected-(J1310-Pad92)") (class "Default")
      (node (ref "J1310") (pin "92") (pinfunction "92_92") (pintype "passive+no_connect"))
    )
    (net (code "169") (name "unconnected-(J1311-Pad3)") (class "Default")
      (node (ref "J1311") (pin "3") (pinfunction "3_3") (pintype "passive+no_connect"))
    )
    (net (code "170") (name "unconnected-(J1311-Pad5)") (class "Default")
      (node (ref "J1311") (pin "5") (pinfunction "5_5") (pintype "passive+no_connect"))
    )
    (net (code "171") (name "unconnected-(J1311-Pad9)") (class "Default")
      (node (ref "J1311") (pin "9") (pinfunction "9_9") (pintype "passive+no_connect"))
    )
    (net (code "172") (name "unconnected-(J1311-Pad11)") (class "Default")
      (node (ref "J1311") (pin "11") (pinfunction "11_11") (pintype "passive+no_connect"))
    )
    (net (code "173") (name "unconnected-(J1311-Pad15)") (class "Default")
      (node (ref "J1311") (pin "15") (pinfunction "15_15") (pintype "passive+no_connect"))
    )
    (net (code "174") (name "unconnected-(J1311-Pad17)") (class "Default")
      (node (ref "J1311") (pin "17") (pinfunction "17_17") (pintype "passive+no_connect"))
    )
    (net (code "175") (name "unconnected-(J1311-Pad22)") (class "Default")
      (node (ref "J1311") (pin "22") (pinfunction "22_22") (pintype "passive+no_connect"))
    )
    (net (code "176") (name "unconnected-(J1311-Pad24)") (class "Default")
      (node (ref "J1311") (pin "24") (pinfunction "24_24") (pintype "passive+no_connect"))
    )
    (net (code "177") (name "unconnected-(J1311-Pad28)") (class "Default")
      (node (ref "J1311") (pin "28") (pinfunction "28_28") (pintype "passive+no_connect"))
    )
    (net (code "178") (name "unconnected-(J1311-Pad30)") (class "Default")
      (node (ref "J1311") (pin "30") (pinfunction "30_30") (pintype "passive+no_connect"))
    )
    (net (code "179") (name "unconnected-(J1311-Pad33)") (class "Default")
      (node (ref "J1311") (pin "33") (pinfunction "33_33") (pintype "passive+no_connect"))
    )
    (net (code "180") (name "unconnected-(J1311-Pad34)") (class "Default")
      (node (ref "J1311") (pin "34") (pinfunction "34_34") (pintype "passive+no_connect"))
    )
    (net (code "181") (name "unconnected-(J1311-Pad35)") (class "Default")
      (node (ref "J1311") (pin "35") (pinfunction "35_35") (pintype "passive+no_connect"))
    )
    (net (code "182") (name "unconnected-(J1311-Pad36)") (class "Default")
      (node (ref "J1311") (pin "36") (pinfunction "36_36") (pintype "passive+no_connect"))
    )
    (net (code "183") (name "unconnected-(J1311-Pad39)") (class "Default")
      (node (ref "J1311") (pin "39") (pinfunction "39_39") (pintype "passive+no_connect"))
    )
    (net (code "184") (name "unconnected-(J1311-Pad41)") (class "Default")
      (node (ref "J1311") (pin "41") (pinfunction "41_41") (pintype "passive+no_connect"))
    )
    (net (code "185") (name "unconnected-(J1311-Pad78)") (class "Default")
      (node (ref "J1311") (pin "78") (pinfunction "78_78") (pintype "passive+no_connect"))
    )
    (net (code "186") (name "unconnected-(J1311-Pad88)") (class "Default")
      (node (ref "J1311") (pin "88") (pinfunction "88_88") (pintype "passive+no_connect"))
    )
    (net (code "187") (name "unconnected-(J1311-Pad92)") (class "Default")
      (node (ref "J1311") (pin "92") (pinfunction "92_92") (pintype "passive+no_connect"))
    )
    (net (code "188") (name "unconnected-(J1311-Pad96)") (class "Default")
      (node (ref "J1311") (pin "96") (pinfunction "96_96") (pintype "passive+no_connect"))
    )
    (net (code "189") (name "unconnected-(J1312-Pad6)") (class "Default")
      (node (ref "J1312") (pin "6") (pinfunction "6_6") (pintype "passive+no_connect"))
    )
    (net (code "190") (name "unconnected-(J1312-Pad13)") (class "Default")
      (node (ref "J1312") (pin "13") (pinfunction "13_13") (pintype "passive+no_connect"))
    )
    (net (code "191") (name "unconnected-(J1312-Pad15)") (class "Default")
      (node (ref "J1312") (pin "15") (pinfunction "15_15") (pintype "passive+no_connect"))
    )
    (net (code "192") (name "unconnected-(J1312-Pad17)") (class "Default")
      (node (ref "J1312") (pin "17") (pinfunction "17_17") (pintype "passive+no_connect"))
    )
    (net (code "193") (name "unconnected-(J1312-Pad19)") (class "Default")
      (node (ref "J1312") (pin "19") (pinfunction "19_19") (pintype "passive+no_connect"))
    )
    (net (code "194") (name "unconnected-(J1312-Pad21)") (class "Default")
      (node (ref "J1312") (pin "21") (pinfunction "21_21") (pintype "passive+no_connect"))
    )
    (net (code "195") (name "unconnected-(J1312-Pad23)") (class "Default")
      (node (ref "J1312") (pin "23") (pinfunction "23_23") (pintype "passive+no_connect"))
    )
    (net (code "196") (name "unconnected-(J1312-Pad25)") (class "Default")
      (node (ref "J1312") (pin "25") (pinfunction "25_25") (pintype "passive+no_connect"))
    )
    (net (code "197") (name "unconnected-(J1312-Pad26)") (class "Default")
      (node (ref "J1312") (pin "26") (pinfunction "26_26") (pintype "passive+no_connect"))
    )
    (net (code "198") (name "unconnected-(J1312-Pad27)") (class "Default")
      (node (ref "J1312") (pin "27") (pinfunction "27_27") (pintype "passive+no_connect"))
    )
    (net (code "199") (name "unconnected-(J1312-Pad29)") (class "Default")
      (node (ref "J1312") (pin "29") (pinfunction "29_29") (pintype "passive+no_connect"))
    )
    (net (code "200") (name "unconnected-(J1312-Pad31)") (class "Default")
      (node (ref "J1312") (pin "31") (pinfunction "31_31") (pintype "passive+no_connect"))
    )
    (net (code "201") (name "unconnected-(J1312-Pad35)") (class "Default")
      (node (ref "J1312") (pin "35") (pinfunction "35_35") (pintype "passive+no_connect"))
    )
    (net (code "202") (name "unconnected-(J1312-Pad36)") (class "Default")
      (node (ref "J1312") (pin "36") (pinfunction "36_36") (pintype "passive+no_connect"))
    )
    (net (code "203") (name "unconnected-(J1312-Pad37)") (class "Default")
      (node (ref "J1312") (pin "37") (pinfunction "37_37") (pintype "passive+no_connect"))
    )
    (net (code "204") (name "unconnected-(J1312-Pad41)") (class "Default")
      (node (ref "J1312") (pin "41") (pinfunction "41_41") (pintype "passive+no_connect"))
    )
    (net (code "205") (name "unconnected-(J1312-Pad42)") (class "Default")
      (node (ref "J1312") (pin "42") (pinfunction "42_42") (pintype "passive+no_connect"))
    )
    (net (code "206") (name "unconnected-(J1312-Pad67)") (class "Default")
      (node (ref "J1312") (pin "67") (pinfunction "67_67") (pintype "passive+no_connect"))
    )
    (net (code "207") (name "unconnected-(J1312-Pad69)") (class "Default")
      (node (ref "J1312") (pin "69") (pinfunction "69_69") (pintype "passive+no_connect"))
    )
  )
)
